# TeamI_PDSschematic.net
KiCad netlist of a schematic drawn in EAGLE
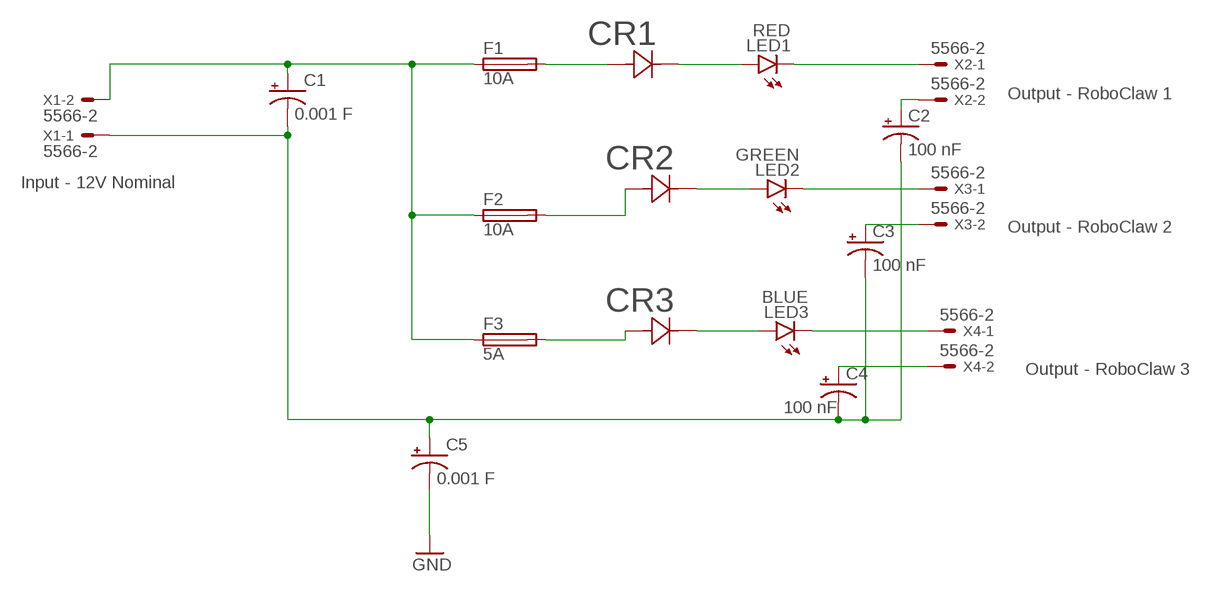
[diagram p0: schematic, sheet 1]

(export (version "E")
  (design (tool "Eeschema 10.0.6"))
  (components
    (comp (ref "C1")
      (value "0.001 F")
      (footprint "eagle-import:E2,5-6")
      (libsource (lib "eagle-import") (part "CPOL-USE2.5-6"))
    )
    (comp (ref "C2")
      (value "100 nF")
      (footprint "eagle-import:E2,5-6")
      (libsource (lib "eagle-import") (part "CPOL-USE2.5-6"))
    )
    (comp (ref "C3")
      (value "100 nF")
      (footprint "eagle-import:E2,5-6")
      (libsource (lib "eagle-import") (part "CPOL-USE2.5-6"))
    )
    (comp (ref "C4")
      (value "100 nF")
      (footprint "eagle-import:E2,5-6")
      (libsource (lib "eagle-import") (part "CPOL-USE2.5-6"))
    )
    (comp (ref "C5")
      (value "0.001 F")
      (footprint "eagle-import:E2,5-6")
      (libsource (lib "eagle-import") (part "CPOL-USE2.5-6"))
    )
    (comp (ref "CR1")
      (value "SMAJ26A-E3/61")
      (footprint "eagle-import:DIODE_DO-214AC")
      (fields (field (name "COPYRIGHT") "Copyright (C) 2025 Ultra Librarian. All rights reserved."))
      (libsource (lib "eagle-import") (part "SMAJ26A-E3/61"))
    )
    (comp (ref "CR2")
      (value "SMAJ26A-E3/61")
      (footprint "eagle-import:DIODE_DO-214AC")
      (fields (field (name "COPYRIGHT") "Copyright (C) 2025 Ultra Librarian. All rights reserved."))
      (libsource (lib "eagle-import") (part "SMAJ26A-E3/61"))
    )
    (comp (ref "CR3")
      (value "SMAJ26A-E3/61")
      (footprint "eagle-import:DIODE_DO-214AC")
      (fields (field (name "COPYRIGHT") "Copyright (C) 2025 Ultra Librarian. All rights reserved."))
      (libsource (lib "eagle-import") (part "SMAJ26A-E3/61"))
    )
    (comp (ref "F1")
      (value "10A")
      (footprint "eagle-import:TE5")
      (libsource (lib "eagle-import") (part "TE5"))
    )
    (comp (ref "F2")
      (value "10A")
      (footprint "eagle-import:TE5")
      (libsource (lib "eagle-import") (part "TE5"))
    )
    (comp (ref "F3")
      (value "5A")
      (footprint "eagle-import:TE5")
      (libsource (lib "eagle-import") (part "TE5"))
    )
    (comp (ref "LED1")
      (value "RED")
      (footprint "eagle-import:1206")
      (libsource (lib "eagle-import") (part "LEDSMT1206"))
    )
    (comp (ref "LED2")
      (value "GREEN")
      (footprint "eagle-import:1206")
      (libsource (lib "eagle-import") (part "LEDSMT1206"))
    )
    (comp (ref "LED3")
      (value "BLUE")
      (footprint "eagle-import:1206")
      (libsource (lib "eagle-import") (part "LEDSMT1206"))
    )
    (comp (ref "X1")
      (value "5566-2")
      (footprint "eagle-import:5566-2")
      (fields (field (name "MF") "MOLEX"))
      (libsource (lib "eagle-import") (part "5566-2"))
    )
    (comp (ref "X2")
      (value "5566-2")
      (footprint "eagle-import:5566-2")
      (fields (field (name "MF") "MOLEX"))
      (libsource (lib "eagle-import") (part "5566-2"))
    )
    (comp (ref "X3")
      (value "5566-2")
      (footprint "eagle-import:5566-2")
      (fields (field (name "MF") "MOLEX"))
      (libsource (lib "eagle-import") (part "5566-2"))
    )
    (comp (ref "X4")
      (value "5566-2")
      (footprint "eagle-import:5566-2")
      (fields (field (name "MF") "MOLEX"))
      (libsource (lib "eagle-import") (part "5566-2"))
    )
  )
  (nets
    (net (code "1") (name "GND") (class "Default")
      (node (ref "C5") (pin "-") (pinfunction "-_-") (pintype "passive"))
    )
    (net (code "2") (name "Net-(CR1-Pad1)") (class "Default")
      (node (ref "CR1") (pin "1") (pinfunction "1_1") (pintype "passive"))
      (node (ref "LED1") (pin "A") (pinfunction "A_A") (pintype "passive"))
    )
    (net (code "3") (name "Net-(CR1-Pad2)") (class "Default")
      (node (ref "CR1") (pin "2") (pinfunction "2_2") (pintype "passive"))
      (node (ref "F1") (pin "2") (pinfunction "2_2") (pintype "passive"))
    )
    (net (code "4") (name "Net-(CR2-Pad1)") (class "Default")
      (node (ref "CR2") (pin "1") (pinfunction "1_1") (pintype "passive"))
      (node (ref "LED2") (pin "A") (pinfunction "A_A") (pintype "passive"))
    )
    (net (code "5") (name "Net-(CR2-Pad2)") (class "Default")
      (node (ref "CR2") (pin "2") (pinfunction "2_2") (pintype "passive"))
      (node (ref "F2") (pin "2") (pinfunction "2_2") (pintype "passive"))
    )
    (net (code "6") (name "Net-(CR3-Pad1)") (class "Default")
      (node (ref "CR3") (pin "1") (pinfunction "1_1") (pintype "passive"))
      (node (ref "LED3") (pin "A") (pinfunction "A_A") (pintype "passive"))
    )
    (net (code "7") (name "Net-(CR3-Pad2)") (class "Default")
      (node (ref "CR3") (pin "2") (pinfunction "2_2") (pintype "passive"))
      (node (ref "F3") (pin "2") (pinfunction "2_2") (pintype "passive"))
    )
    (net (code "8") (name "Net-(X1A-S)") (class "Default")
      (node (ref "C1") (pin "-") (pinfunction "-_-") (pintype "passive"))
      (node (ref "C2") (pin "-") (pinfunction "-_-") (pintype "passive"))
      (node (ref "C3") (pin "-") (pinfunction "-_-") (pintype "passive"))
      (node (ref "C4") (pin "-") (pinfunction "-_-") (pintype "passive"))
      (node (ref "C5") (pin "+") (pinfunction "+_+") (pintype "passive"))
      (node (ref "X1") (pin "1") (pinfunction "S_1") (pintype "passive"))
    )
    (net (code "9") (name "Net-(X1B-S)") (class "Default")
      (node (ref "C1") (pin "+") (pinfunction "+_+") (pintype "passive"))
      (node (ref "F1") (pin "1") (pinfunction "1_1") (pintype "passive"))
      (node (ref "F2") (pin "1") (pinfunction "1_1") (pintype "passive"))
      (node (ref "F3") (pin "1") (pinfunction "1_1") (pintype "passive"))
      (node (ref "X1") (pin "2") (pinfunction "S_2") (pintype "passive"))
    )
    (net (code "10") (name "Net-(X2A-S)") (class "Default")
      (node (ref "LED1") (pin "C") (pinfunction "C_C") (pintype "passive"))
      (node (ref "X2") (pin "1") (pinfunction "S_1") (pintype "passive"))
    )
    (net (code "11") (name "Net-(X2B-S)") (class "Default")
      (node (ref "C2") (pin "+") (pinfunction "+_+") (pintype "passive"))
      (node (ref "X2") (pin "2") (pinfunction "S_2") (pintype "passive"))
    )
    (net (code "12") (name "Net-(X3A-S)") (class "Default")
      (node (ref "LED2") (pin "C") (pinfunction "C_C") (pintype "passive"))
      (node (ref "X3") (pin "1") (pinfunction "S_1") (pintype "passive"))
    )
    (net (code "13") (name "Net-(X3B-S)") (class "Default")
      (node (ref "C3") (pin "+") (pinfunction "+_+") (pintype "passive"))
      (node (ref "X3") (pin "2") (pinfunction "S_2") (pintype "passive"))
    )
    (net (code "14") (name "Net-(X4A-S)") (class "Default")
      (node (ref "LED3") (pin "C") (pinfunction "C_C") (pintype "passive"))
      (node (ref "X4") (pin "1") (pinfunction "S_1") (pintype "passive"))
    )
    (net (code "15") (name "Net-(X4B-S)") (class "Default")
      (node (ref "C4") (pin "+") (pinfunction "+_+") (pintype "passive"))
      (node (ref "X4") (pin "2") (pinfunction "S_2") (pintype "passive"))
    )
  )
)
